# Stimulation_Testbed_Expansion_V2.net
KiCad netlist of a schematic drawn in EAGLE
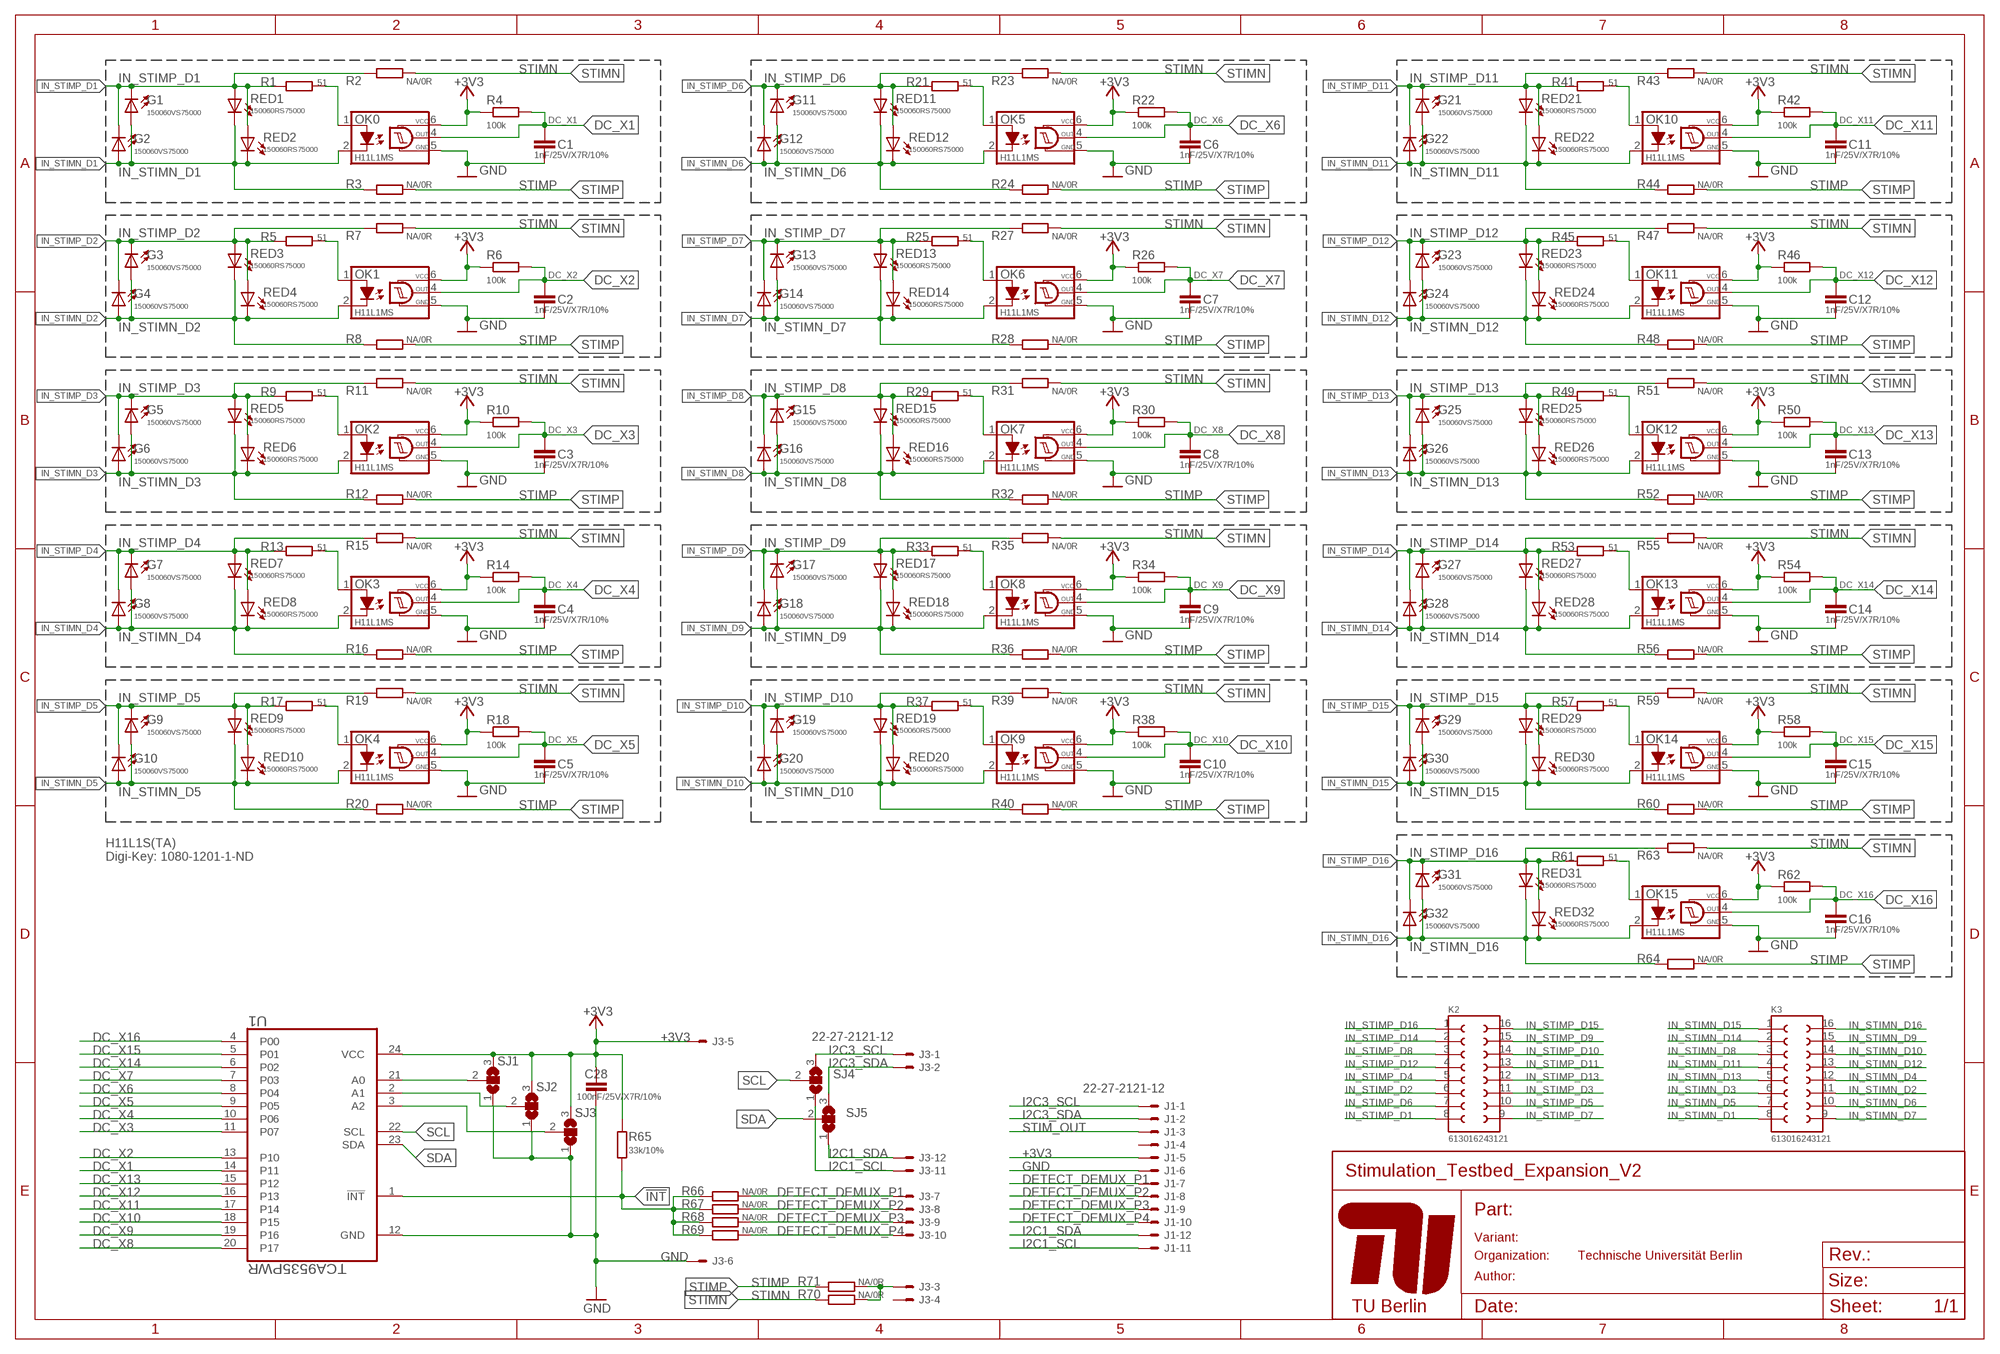
[diagram p0: schematic, sheet 1]

(export (version "E")
  (design (tool "Eeschema 10.0.6"))
  (components
    (comp (ref "C1")
      (value "1nF/25V/X7R/10%")
      (footprint "eagle-import:C0603")
      (libsource (lib "eagle-import") (part "C-EUC0603"))
    )
    (comp (ref "C2")
      (value "1nF/25V/X7R/10%")
      (footprint "eagle-import:C0603")
      (libsource (lib "eagle-import") (part "C-EUC0603"))
    )
    (comp (ref "C3")
      (value "1nF/25V/X7R/10%")
      (footprint "eagle-import:C0603")
      (libsource (lib "eagle-import") (part "C-EUC0603"))
    )
    (comp (ref "C4")
      (value "1nF/25V/X7R/10%")
      (footprint "eagle-import:C0603")
      (libsource (lib "eagle-import") (part "C-EUC0603"))
    )
    (comp (ref "C5")
      (value "1nF/25V/X7R/10%")
      (footprint "eagle-import:C0603")
      (libsource (lib "eagle-import") (part "C-EUC0603"))
    )
    (comp (ref "C6")
      (value "1nF/25V/X7R/10%")
      (footprint "eagle-import:C0603")
      (libsource (lib "eagle-import") (part "C-EUC0603"))
    )
    (comp (ref "C7")
      (value "1nF/25V/X7R/10%")
      (footprint "eagle-import:C0603")
      (libsource (lib "eagle-import") (part "C-EUC0603"))
    )
    (comp (ref "C8")
      (value "1nF/25V/X7R/10%")
      (footprint "eagle-import:C0603")
      (libsource (lib "eagle-import") (part "C-EUC0603"))
    )
    (comp (ref "C9")
      (value "1nF/25V/X7R/10%")
      (footprint "eagle-import:C0603")
      (libsource (lib "eagle-import") (part "C-EUC0603"))
    )
    (comp (ref "C10")
      (value "1nF/25V/X7R/10%")
      (footprint "eagle-import:C0603")
      (libsource (lib "eagle-import") (part "C-EUC0603"))
    )
    (comp (ref "C11")
      (value "1nF/25V/X7R/10%")
      (footprint "eagle-import:C0603")
      (libsource (lib "eagle-import") (part "C-EUC0603"))
    )
    (comp (ref "C12")
      (value "1nF/25V/X7R/10%")
      (footprint "eagle-import:C0603")
      (libsource (lib "eagle-import") (part "C-EUC0603"))
    )
    (comp (ref "C13")
      (value "1nF/25V/X7R/10%")
      (footprint "eagle-import:C0603")
      (libsource (lib "eagle-import") (part "C-EUC0603"))
    )
    (comp (ref "C14")
      (value "1nF/25V/X7R/10%")
      (footprint "eagle-import:C0603")
      (libsource (lib "eagle-import") (part "C-EUC0603"))
    )
    (comp (ref "C15")
      (value "1nF/25V/X7R/10%")
      (footprint "eagle-import:C0603")
      (libsource (lib "eagle-import") (part "C-EUC0603"))
    )
    (comp (ref "C16")
      (value "1nF/25V/X7R/10%")
      (footprint "eagle-import:C0603")
      (libsource (lib "eagle-import") (part "C-EUC0603"))
    )
    (comp (ref "C28")
      (value "100nF/25V/X7R/10%")
      (footprint "eagle-import:C0603K")
      (libsource (lib "eagle-import") (part "C-EUC0603K"))
    )
    (comp (ref "G1")
      (value "150060VS75000")
      (footprint "eagle-import:CHIPLED_0603")
      (libsource (lib "eagle-import") (part "LEDCHIPLED_0603"))
    )
    (comp (ref "G2")
      (value "150060VS75000")
      (footprint "eagle-import:CHIPLED_0603")
      (libsource (lib "eagle-import") (part "LEDCHIPLED_0603"))
    )
    (comp (ref "G3")
      (value "150060VS75000")
      (footprint "eagle-import:CHIPLED_0603")
      (libsource (lib "eagle-import") (part "LEDCHIPLED_0603"))
    )
    (comp (ref "G4")
      (value "150060VS75000")
      (footprint "eagle-import:CHIPLED_0603")
      (libsource (lib "eagle-import") (part "LEDCHIPLED_0603"))
    )
    (comp (ref "G5")
      (value "150060VS75000")
      (footprint "eagle-import:CHIPLED_0603")
      (libsource (lib "eagle-import") (part "LEDCHIPLED_0603"))
    )
    (comp (ref "G6")
      (value "150060VS75000")
      (footprint "eagle-import:CHIPLED_0603")
      (libsource (lib "eagle-import") (part "LEDCHIPLED_0603"))
    )
    (comp (ref "G7")
      (value "150060VS75000")
      (footprint "eagle-import:CHIPLED_0603")
      (libsource (lib "eagle-import") (part "LEDCHIPLED_0603"))
    )
    (comp (ref "G8")
      (value "150060VS75000")
      (footprint "eagle-import:CHIPLED_0603")
      (libsource (lib "eagle-import") (part "LEDCHIPLED_0603"))
    )
    (comp (ref "G9")
      (value "150060VS75000")
      (footprint "eagle-import:CHIPLED_0603")
      (libsource (lib "eagle-import") (part "LEDCHIPLED_0603"))
    )
    (comp (ref "G10")
      (value "150060VS75000")
      (footprint "eagle-import:CHIPLED_0603")
      (libsource (lib "eagle-import") (part "LEDCHIPLED_0603"))
    )
    (comp (ref "G11")
      (value "150060VS75000")
      (footprint "eagle-import:CHIPLED_0603")
      (libsource (lib "eagle-import") (part "LEDCHIPLED_0603"))
    )
    (comp (ref "G12")
      (value "150060VS75000")
      (footprint "eagle-import:CHIPLED_0603")
      (libsource (lib "eagle-import") (part "LEDCHIPLED_0603"))
    )
    (comp (ref "G13")
      (value "150060VS75000")
      (footprint "eagle-import:CHIPLED_0603")
      (libsource (lib "eagle-import") (part "LEDCHIPLED_0603"))
    )
    (comp (ref "G14")
      (value "150060VS75000")
      (footprint "eagle-import:CHIPLED_0603")
      (libsource (lib "eagle-import") (part "LEDCHIPLED_0603"))
    )
    (comp (ref "G15")
      (value "150060VS75000")
      (footprint "eagle-import:CHIPLED_0603")
      (libsource (lib "eagle-import") (part "LEDCHIPLED_0603"))
    )
    (comp (ref "G16")
      (value "150060VS75000")
      (footprint "eagle-import:CHIPLED_0603")
      (libsource (lib "eagle-import") (part "LEDCHIPLED_0603"))
    )
    (comp (ref "G17")
      (value "150060VS75000")
      (footprint "eagle-import:CHIPLED_0603")
      (libsource (lib "eagle-import") (part "LEDCHIPLED_0603"))
    )
    (comp (ref "G18")
      (value "150060VS75000")
      (footprint "eagle-import:CHIPLED_0603")
      (libsource (lib "eagle-import") (part "LEDCHIPLED_0603"))
    )
    (comp (ref "G19")
      (value "150060VS75000")
      (footprint "eagle-import:CHIPLED_0603")
      (libsource (lib "eagle-import") (part "LEDCHIPLED_0603"))
    )
    (comp (ref "G20")
      (value "150060VS75000")
      (footprint "eagle-import:CHIPLED_0603")
      (libsource (lib "eagle-import") (part "LEDCHIPLED_0603"))
    )
    (comp (ref "G21")
      (value "150060VS75000")
      (footprint "eagle-import:CHIPLED_0603")
      (libsource (lib "eagle-import") (part "LEDCHIPLED_0603"))
    )
    (comp (ref "G22")
      (value "150060VS75000")
      (footprint "eagle-import:CHIPLED_0603")
      (libsource (lib "eagle-import") (part "LEDCHIPLED_0603"))
    )
    (comp (ref "G23")
      (value "150060VS75000")
      (footprint "eagle-import:CHIPLED_0603")
      (libsource (lib "eagle-import") (part "LEDCHIPLED_0603"))
    )
    (comp (ref "G24")
      (value "150060VS75000")
      (footprint "eagle-import:CHIPLED_0603")
      (libsource (lib "eagle-import") (part "LEDCHIPLED_0603"))
    )
    (comp (ref "G25")
      (value "150060VS75000")
      (footprint "eagle-import:CHIPLED_0603")
      (libsource (lib "eagle-import") (part "LEDCHIPLED_0603"))
    )
    (comp (ref "G26")
      (value "150060VS75000")
      (footprint "eagle-import:CHIPLED_0603")
      (libsource (lib "eagle-import") (part "LEDCHIPLED_0603"))
    )
    (comp (ref "G27")
      (value "150060VS75000")
      (footprint "eagle-import:CHIPLED_0603")
      (libsource (lib "eagle-import") (part "LEDCHIPLED_0603"))
    )
    (comp (ref "G28")
      (value "150060VS75000")
      (footprint "eagle-import:CHIPLED_0603")
      (libsource (lib "eagle-import") (part "LEDCHIPLED_0603"))
    )
    (comp (ref "G29")
      (value "150060VS75000")
      (footprint "eagle-import:CHIPLED_0603")
      (libsource (lib "eagle-import") (part "LEDCHIPLED_0603"))
    )
    (comp (ref "G30")
      (value "150060VS75000")
      (footprint "eagle-import:CHIPLED_0603")
      (libsource (lib "eagle-import") (part "LEDCHIPLED_0603"))
    )
    (comp (ref "G31")
      (value "150060VS75000")
      (footprint "eagle-import:CHIPLED_0603")
      (libsource (lib "eagle-import") (part "LEDCHIPLED_0603"))
    )
    (comp (ref "G32")
      (value "150060VS75000")
      (footprint "eagle-import:CHIPLED_0603")
      (libsource (lib "eagle-import") (part "LEDCHIPLED_0603"))
    )
    (comp (ref "J1")
      (value "22-27-2121-12")
      (footprint "eagle-import:6410-12")
      (libsource (lib "eagle-import") (part "22-?-1227-2121"))
    )
    (comp (ref "J3")
      (value "22-27-2121-12")
      (footprint "eagle-import:6410-12")
      (libsource (lib "eagle-import") (part "22-?-1227-2121"))
    )
    (comp (ref "K2")
      (value "613016243121")
      (footprint "eagle-import:613016243121")
      (libsource (lib "eagle-import") (part "613016243121"))
    )
    (comp (ref "K3")
      (value "613016243121")
      (footprint "eagle-import:613016243121")
      (libsource (lib "eagle-import") (part "613016243121"))
    )
    (comp (ref "OK0")
      (value "H11L1MS")
      (footprint "eagle-import:DIL6-SMD")
      (libsource (lib "eagle-import") (part "H11LMS1"))
    )
    (comp (ref "OK1")
      (value "H11L1MS")
      (footprint "eagle-import:DIL6-SMD")
      (libsource (lib "eagle-import") (part "H11LMS1"))
    )
    (comp (ref "OK2")
      (value "H11L1MS")
      (footprint "eagle-import:DIL6-SMD")
      (libsource (lib "eagle-import") (part "H11LMS1"))
    )
    (comp (ref "OK3")
      (value "H11L1MS")
      (footprint "eagle-import:DIL6-SMD")
      (libsource (lib "eagle-import") (part "H11LMS1"))
    )
    (comp (ref "OK4")
      (value "H11L1MS")
      (footprint "eagle-import:DIL6-SMD")
      (libsource (lib "eagle-import") (part "H11LMS1"))
    )
    (comp (ref "OK5")
      (value "H11L1MS")
      (footprint "eagle-import:DIL6-SMD")
      (libsource (lib "eagle-import") (part "H11LMS1"))
    )
    (comp (ref "OK6")
      (value "H11L1MS")
      (footprint "eagle-import:DIL6-SMD")
      (libsource (lib "eagle-import") (part "H11LMS1"))
    )
    (comp (ref "OK7")
      (value "H11L1MS")
      (footprint "eagle-import:DIL6-SMD")
      (libsource (lib "eagle-import") (part "H11LMS1"))
    )
    (comp (ref "OK8")
      (value "H11L1MS")
      (footprint "eagle-import:DIL6-SMD")
      (libsource (lib "eagle-import") (part "H11LMS1"))
    )
    (comp (ref "OK9")
      (value "H11L1MS")
      (footprint "eagle-import:DIL6-SMD")
      (libsource (lib "eagle-import") (part "H11LMS1"))
    )
    (comp (ref "OK10")
      (value "H11L1MS")
      (footprint "eagle-import:DIL6-SMD")
      (libsource (lib "eagle-import") (part "H11LMS1"))
    )
    (comp (ref "OK11")
      (value "H11L1MS")
      (footprint "eagle-import:DIL6-SMD")
      (libsource (lib "eagle-import") (part "H11LMS1"))
    )
    (comp (ref "OK12")
      (value "H11L1MS")
      (footprint "eagle-import:DIL6-SMD")
      (libsource (lib "eagle-import") (part "H11LMS1"))
    )
    (comp (ref "OK13")
      (value "H11L1MS")
      (footprint "eagle-import:DIL6-SMD")
      (libsource (lib "eagle-import") (part "H11LMS1"))
    )
    (comp (ref "OK14")
      (value "H11L1MS")
      (footprint "eagle-import:DIL6-SMD")
      (libsource (lib "eagle-import") (part "H11LMS1"))
    )
    (comp (ref "OK15")
      (value "H11L1MS")
      (footprint "eagle-import:DIL6-SMD")
      (libsource (lib "eagle-import") (part "H11LMS1"))
    )
    (comp (ref "R1")
      (value "51")
      (footprint "eagle-import:R0603")
      (libsource (lib "eagle-import") (part "R-EU_R0603"))
    )
    (comp (ref "R2")
      (value "NA/0R")
      (footprint "eagle-import:R0603")
      (libsource (lib "eagle-import") (part "R-EU_R0603"))
    )
    (comp (ref "R3")
      (value "NA/0R")
      (footprint "eagle-import:R0603")
      (libsource (lib "eagle-import") (part "R-EU_R0603"))
    )
    (comp (ref "R4")
      (value "100k")
      (footprint "eagle-import:R0603")
      (libsource (lib "eagle-import") (part "R-EU_R0603"))
    )
    (comp (ref "R5")
      (value "51")
      (footprint "eagle-import:R0603")
      (libsource (lib "eagle-import") (part "R-EU_R0603"))
    )
    (comp (ref "R6")
      (value "100k")
      (footprint "eagle-import:R0603")
      (libsource (lib "eagle-import") (part "R-EU_R0603"))
    )
    (comp (ref "R7")
      (value "NA/0R")
      (footprint "eagle-import:R0603")
      (libsource (lib "eagle-import") (part "R-EU_R0603"))
    )
    (comp (ref "R8")
      (value "NA/0R")
      (footprint "eagle-import:R0603")
      (libsource (lib "eagle-import") (part "R-EU_R0603"))
    )
    (comp (ref "R9")
      (value "51")
      (footprint "eagle-import:R0603")
      (libsource (lib "eagle-import") (part "R-EU_R0603"))
    )
    (comp (ref "R10")
      (value "100k")
      (footprint "eagle-import:R0603")
      (libsource (lib "eagle-import") (part "R-EU_R0603"))
    )
    (comp (ref "R11")
      (value "NA/0R")
      (footprint "eagle-import:R0603")
      (libsource (lib "eagle-import") (part "R-EU_R0603"))
    )
    (comp (ref "R12")
      (value "NA/0R")
      (footprint "eagle-import:R0603")
      (libsource (lib "eagle-import") (part "R-EU_R0603"))
    )
    (comp (ref "R13")
      (value "51")
      (footprint "eagle-import:R0603")
      (libsource (lib "eagle-import") (part "R-EU_R0603"))
    )
    (comp (ref "R14")
      (value "100k")
      (footprint "eagle-import:R0603")
      (libsource (lib "eagle-import") (part "R-EU_R0603"))
    )
    (comp (ref "R15")
      (value "NA/0R")
      (footprint "eagle-import:R0603")
      (libsource (lib "eagle-import") (part "R-EU_R0603"))
    )
    (comp (ref "R16")
      (value "NA/0R")
      (footprint "eagle-import:R0603")
      (libsource (lib "eagle-import") (part "R-EU_R0603"))
    )
    (comp (ref "R17")
      (value "51")
      (footprint "eagle-import:R0603")
      (libsource (lib "eagle-import") (part "R-EU_R0603"))
    )
    (comp (ref "R18")
      (value "100k")
      (footprint "eagle-import:R0603")
      (libsource (lib "eagle-import") (part "R-EU_R0603"))
    )
    (comp (ref "R19")
      (value "NA/0R")
      (footprint "eagle-import:R0603")
      (libsource (lib "eagle-import") (part "R-EU_R0603"))
    )
    (comp (ref "R20")
      (value "NA/0R")
      (footprint "eagle-import:R0603")
      (libsource (lib "eagle-import") (part "R-EU_R0603"))
    )
    (comp (ref "R21")
      (value "51")
      (footprint "eagle-import:R0603")
      (libsource (lib "eagle-import") (part "R-EU_R0603"))
    )
    (comp (ref "R22")
      (value "100k")
      (footprint "eagle-import:R0603")
      (libsource (lib "eagle-import") (part "R-EU_R0603"))
    )
    (comp (ref "R23")
      (value "NA/0R")
      (footprint "eagle-import:R0603")
      (libsource (lib "eagle-import") (part "R-EU_R0603"))
    )
    (comp (ref "R24")
      (value "NA/0R")
      (footprint "eagle-import:R0603")
      (libsource (lib "eagle-import") (part "R-EU_R0603"))
    )
    (comp (ref "R25")
      (value "51")
      (footprint "eagle-import:R0603")
      (libsource (lib "eagle-import") (part "R-EU_R0603"))
    )
    (comp (ref "R26")
      (value "100k")
      (footprint "eagle-import:R0603")
      (libsource (lib "eagle-import") (part "R-EU_R0603"))
    )
    (comp (ref "R27")
      (value "NA/0R")
      (footprint "eagle-import:R0603")
      (libsource (lib "eagle-import") (part "R-EU_R0603"))
    )
    (comp (ref "R28")
      (value "NA/0R")
      (footprint "eagle-import:R0603")
      (libsource (lib "eagle-import") (part "R-EU_R0603"))
    )
    (comp (ref "R29")
      (value "51")
      (footprint "eagle-import:R0603")
      (libsource (lib "eagle-import") (part "R-EU_R0603"))
    )
    (comp (ref "R30")
      (value "100k")
      (footprint "eagle-import:R0603")
      (libsource (lib "eagle-import") (part "R-EU_R0603"))
    )
    (comp (ref "R31")
      (value "NA/0R")
      (footprint "eagle-import:R0603")
      (libsource (lib "eagle-import") (part "R-EU_R0603"))
    )
    (comp (ref "R32")
      (value "NA/0R")
      (footprint "eagle-import:R0603")
      (libsource (lib "eagle-import") (part "R-EU_R0603"))
    )
    (comp (ref "R33")
      (value "51")
      (footprint "eagle-import:R0603")
      (libsource (lib "eagle-import") (part "R-EU_R0603"))
    )
    (comp (ref "R34")
      (value "100k")
      (footprint "eagle-import:R0603")
      (libsource (lib "eagle-import") (part "R-EU_R0603"))
    )
    (comp (ref "R35")
      (value "NA/0R")
      (footprint "eagle-import:R0603")
      (libsource (lib "eagle-import") (part "R-EU_R0603"))
    )
    (comp (ref "R36")
      (value "NA/0R")
      (footprint "eagle-import:R0603")
      (libsource (lib "eagle-import") (part "R-EU_R0603"))
    )
    (comp (ref "R37")
      (value "51")
      (footprint "eagle-import:R0603")
      (libsource (lib "eagle-import") (part "R-EU_R0603"))
    )
    (comp (ref "R38")
      (value "100k")
      (footprint "eagle-import:R0603")
      (libsource (lib "eagle-import") (part "R-EU_R0603"))
    )
    (comp (ref "R39")
      (value "NA/0R")
      (footprint "eagle-import:R0603")
      (libsource (lib "eagle-import") (part "R-EU_R0603"))
    )
    (comp (ref "R40")
      (value "NA/0R")
      (footprint "eagle-import:R0603")
      (libsource (lib "eagle-import") (part "R-EU_R0603"))
    )
    (comp (ref "R41")
      (value "51")
      (footprint "eagle-import:R0603")
      (libsource (lib "eagle-import") (part "R-EU_R0603"))
    )
    (comp (ref "R42")
      (value "100k")
      (footprint "eagle-import:R0603")
      (libsource (lib "eagle-import") (part "R-EU_R0603"))
    )
    (comp (ref "R43")
      (value "NA/0R")
      (footprint "eagle-import:R0603")
      (libsource (lib "eagle-import") (part "R-EU_R0603"))
    )
    (comp (ref "R44")
      (value "NA/0R")
      (footprint "eagle-import:R0603")
      (libsource (lib "eagle-import") (part "R-EU_R0603"))
    )
    (comp (ref "R45")
      (value "51")
      (footprint "eagle-import:R0603")
      (libsource (lib "eagle-import") (part "R-EU_R0603"))
    )
    (comp (ref "R46")
      (value "100k")
      (footprint "eagle-import:R0603")
      (libsource (lib "eagle-import") (part "R-EU_R0603"))
    )
    (comp (ref "R47")
      (value "NA/0R")
      (footprint "eagle-import:R0603")
      (libsource (lib "eagle-import") (part "R-EU_R0603"))
    )
    (comp (ref "R48")
      (value "NA/0R")
      (footprint "eagle-import:R0603")
      (libsource (lib "eagle-import") (part "R-EU_R0603"))
    )
    (comp (ref "R49")
      (value "51")
      (footprint "eagle-import:R0603")
      (libsource (lib "eagle-import") (part "R-EU_R0603"))
    )
    (comp (ref "R50")
      (value "100k")
      (footprint "eagle-import:R0603")
      (libsource (lib "eagle-import") (part "R-EU_R0603"))
    )
    (comp (ref "R51")
      (value "NA/0R")
      (footprint "eagle-import:R0603")
      (libsource (lib "eagle-import") (part "R-EU_R0603"))
    )
    (comp (ref "R52")
      (value "NA/0R")
      (footprint "eagle-import:R0603")
      (libsource (lib "eagle-import") (part "R-EU_R0603"))
    )
    (comp (ref "R53")
      (value "51")
      (footprint "eagle-import:R0603")
      (libsource (lib "eagle-import") (part "R-EU_R0603"))
    )
    (comp (ref "R54")
      (value "100k")
      (footprint "eagle-import:R0603")
      (libsource (lib "eagle-import") (part "R-EU_R0603"))
    )
    (comp (ref "R55")
      (value "NA/0R")
      (footprint "eagle-import:R0603")
      (libsource (lib "eagle-import") (part "R-EU_R0603"))
    )
    (comp (ref "R56")
      (value "NA/0R")
      (footprint "eagle-import:R0603")
      (libsource (lib "eagle-import") (part "R-EU_R0603"))
    )
    (comp (ref "R57")
      (value "51")
      (footprint "eagle-import:R0603")
      (libsource (lib "eagle-import") (part "R-EU_R0603"))
    )
    (comp (ref "R58")
      (value "100k")
      (footprint "eagle-import:R0603")
      (libsource (lib "eagle-import") (part "R-EU_R0603"))
    )
    (comp (ref "R59")
      (value "NA/0R")
      (footprint "eagle-import:R0603")
      (libsource (lib "eagle-import") (part "R-EU_R0603"))
    )
    (comp (ref "R60")
      (value "NA/0R")
      (footprint "eagle-import:R0603")
      (libsource (lib "eagle-import") (part "R-EU_R0603"))
    )
    (comp (ref "R61")
      (value "51")
      (footprint "eagle-import:R0603")
      (libsource (lib "eagle-import") (part "R-EU_R0603"))
    )
    (comp (ref "R62")
      (value "100k")
      (footprint "eagle-import:R0603")
      (libsource (lib "eagle-import") (part "R-EU_R0603"))
    )
    (comp (ref "R63")
      (value "NA/0R")
      (footprint "eagle-import:R0603")
      (libsource (lib "eagle-import") (part "R-EU_R0603"))
    )
    (comp (ref "R64")
      (value "NA/0R")
      (footprint "eagle-import:R0603")
      (libsource (lib "eagle-import") (part "R-EU_R0603"))
    )
    (comp (ref "R65")
      (value "33k/10%")
      (footprint "eagle-import:R0603")
      (libsource (lib "eagle-import") (part "R-EU_R0603"))
    )
    (comp (ref "R66")
      (value "NA/0R")
      (footprint "eagle-import:R0603")
      (libsource (lib "eagle-import") (part "R-EU_R0603"))
    )
    (comp (ref "R67")
      (value "NA/0R")
      (footprint "eagle-import:R0603")
      (libsource (lib "eagle-import") (part "R-EU_R0603"))
    )
    (comp (ref "R68")
      (value "NA/0R")
      (footprint "eagle-import:R0603")
      (libsource (lib "eagle-import") (part "R-EU_R0603"))
    )
    (comp (ref "R69")
      (value "NA/0R")
      (footprint "eagle-import:R0603")
      (libsource (lib "eagle-import") (part "R-EU_R0603"))
    )
    (comp (ref "R70")
      (value "NA/0R")
      (footprint "eagle-import:R0603")
      (libsource (lib "eagle-import") (part "R-EU_R0603"))
    )
    (comp (ref "R71")
      (value "NA/0R")
      (footprint "eagle-import:R0603")
      (libsource (lib "eagle-import") (part "R-EU_R0603"))
    )
    (comp (ref "RED1")
      (value "150060RS75000")
      (footprint "eagle-import:CHIP-LED0603")
      (libsource (lib "eagle-import") (part "LEDCHIP-LED0603"))
    )
    (comp (ref "RED2")
      (value "150060RS75000")
      (footprint "eagle-import:CHIP-LED0603")
      (libsource (lib "eagle-import") (part "LEDCHIP-LED0603"))
    )
    (comp (ref "RED3")
      (value "150060RS75000")
      (footprint "eagle-import:CHIP-LED0603")
      (libsource (lib "eagle-import") (part "LEDCHIP-LED0603"))
    )
    (comp (ref "RED4")
      (value "150060RS75000")
      (footprint "eagle-import:CHIP-LED0603")
      (libsource (lib "eagle-import") (part "LEDCHIP-LED0603"))
    )
    (comp (ref "RED5")
      (value "150060RS75000")
      (footprint "eagle-import:CHIP-LED0603")
      (libsource (lib "eagle-import") (part "LEDCHIP-LED0603"))
    )
    (comp (ref "RED6")
      (value "150060RS75000")
      (footprint "eagle-import:CHIP-LED0603")
      (libsource (lib "eagle-import") (part "LEDCHIP-LED0603"))
    )
    (comp (ref "RED7")
      (value "150060RS75000")
      (footprint "eagle-import:CHIP-LED0603")
      (libsource (lib "eagle-import") (part "LEDCHIP-LED0603"))
    )
    (comp (ref "RED8")
      (value "150060RS75000")
      (footprint "eagle-import:CHIP-LED0603")
      (libsource (lib "eagle-import") (part "LEDCHIP-LED0603"))
    )
    (comp (ref "RED9")
      (value "150060RS75000")
      (footprint "eagle-import:CHIP-LED0603")
      (libsource (lib "eagle-import") (part "LEDCHIP-LED0603"))
    )
    (comp (ref "RED10")
      (value "150060RS75000")
      (footprint "eagle-import:CHIP-LED0603")
      (libsource (lib "eagle-import") (part "LEDCHIP-LED0603"))
    )
    (comp (ref "RED11")
      (value "150060RS75000")
      (footprint "eagle-import:CHIP-LED0603")
      (libsource (lib "eagle-import") (part "LEDCHIP-LED0603"))
    )
    (comp (ref "RED12")
      (value "150060RS75000")
      (footprint "eagle-import:CHIP-LED0603")
      (libsource (lib "eagle-import") (part "LEDCHIP-LED0603"))
    )
    (comp (ref "RED13")
      (value "150060RS75000")
      (footprint "eagle-import:CHIP-LED0603")
      (libsource (lib "eagle-import") (part "LEDCHIP-LED0603"))
    )
    (comp (ref "RED14")
      (value "150060RS75000")
      (footprint "eagle-import:CHIP-LED0603")
      (libsource (lib "eagle-import") (part "LEDCHIP-LED0603"))
    )
    (comp (ref "RED15")
      (value "150060RS75000")
      (footprint "eagle-import:CHIP-LED0603")
      (libsource (lib "eagle-import") (part "LEDCHIP-LED0603"))
    )
    (comp (ref "RED16")
      (value "150060RS75000")
      (footprint "eagle-import:CHIP-LED0603")
      (libsource (lib "eagle-import") (part "LEDCHIP-LED0603"))
    )
    (comp (ref "RED17")
      (value "150060RS75000")
      (footprint "eagle-import:CHIP-LED0603")
      (libsource (lib "eagle-import") (part "LEDCHIP-LED0603"))
    )
    (comp (ref "RED18")
      (value "150060RS75000")
      (footprint "eagle-import:CHIP-LED0603")
      (libsource (lib "eagle-import") (part "LEDCHIP-LED0603"))
    )
    (comp (ref "RED19")
      (value "150060RS75000")
      (footprint "eagle-import:CHIP-LED0603")
      (libsource (lib "eagle-import") (part "LEDCHIP-LED0603"))
    )
    (comp (ref "RED20")
      (value "150060RS75000")
      (footprint "eagle-import:CHIP-LED0603")
      (libsource (lib "eagle-import") (part "LEDCHIP-LED0603"))
    )
    (comp (ref "RED21")
      (value "150060RS75000")
      (footprint "eagle-import:CHIP-LED0603")
      (libsource (lib "eagle-import") (part "LEDCHIP-LED0603"))
    )
    (comp (ref "RED22")
      (value "150060RS75000")
      (footprint "eagle-import:CHIP-LED0603")
      (libsource (lib "eagle-import") (part "LEDCHIP-LED0603"))
    )
    (comp (ref "RED23")
      (value "150060RS75000")
      (footprint "eagle-import:CHIP-LED0603")
      (libsource (lib "eagle-import") (part "LEDCHIP-LED0603"))
    )
    (comp (ref "RED24")
      (value "150060RS75000")
      (footprint "eagle-import:CHIP-LED0603")
      (libsource (lib "eagle-import") (part "LEDCHIP-LED0603"))
    )
    (comp (ref "RED25")
      (value "150060RS75000")
      (footprint "eagle-import:CHIP-LED0603")
      (libsource (lib "eagle-import") (part "LEDCHIP-LED0603"))
    )
    (comp (ref "RED26")
      (value "150060RS75000")
      (footprint "eagle-import:CHIP-LED0603")
      (libsource (lib "eagle-import") (part "LEDCHIP-LED0603"))
    )
    (comp (ref "RED27")
      (value "150060RS75000")
      (footprint "eagle-import:CHIP-LED0603")
      (libsource (lib "eagle-import") (part "LEDCHIP-LED0603"))
    )
    (comp (ref "RED28")
      (value "150060RS75000")
      (footprint "eagle-import:CHIP-LED0603")
      (libsource (lib "eagle-import") (part "LEDCHIP-LED0603"))
    )
    (comp (ref "RED29")
      (value "150060RS75000")
      (footprint "eagle-import:CHIP-LED0603")
      (libsource (lib "eagle-import") (part "LEDCHIP-LED0603"))
    )
    (comp (ref "RED30")
      (value "150060RS75000")
      (footprint "eagle-import:CHIP-LED0603")
      (libsource (lib "eagle-import") (part "LEDCHIP-LED0603"))
    )
    (comp (ref "RED31")
      (value "150060RS75000")
      (footprint "eagle-import:CHIP-LED0603")
      (libsource (lib "eagle-import") (part "LEDCHIP-LED0603"))
    )
    (comp (ref "RED32")
      (value "150060RS75000")
      (footprint "eagle-import:CHIP-LED0603")
      (libsource (lib "eagle-import") (part "LEDCHIP-LED0603"))
    )
    (comp (ref "SJ1")
      (value "SJ2W")
      (footprint "eagle-import:SJ_2")
      (libsource (lib "eagle-import") (part "SJ2W"))
    )
    (comp (ref "SJ2")
      (value "SJ2W")
      (footprint "eagle-import:SJ_2")
      (libsource (lib "eagle-import") (part "SJ2W"))
    )
    (comp (ref "SJ3")
      (value "SJ2W")
      (footprint "eagle-import:SJ_2")
      (libsource (lib "eagle-import") (part "SJ2W"))
    )
    (comp (ref "SJ4")
      (value "SJ2W")
      (footprint "eagle-import:SJ_2")
      (libsource (lib "eagle-import") (part "SJ2W"))
    )
    (comp (ref "SJ5")
      (value "SJ2W")
      (footprint "eagle-import:SJ_2")
      (libsource (lib "eagle-import") (part "SJ2W"))
    )
    (comp (ref "U1")
      (value "TCA9535PWR")
      (footprint "eagle-import:SOP65P640X120-24N")
      (fields (field (name "MF") "Texas Instruments"))
      (libsource (lib "eagle-import") (part "TCA9535PWR"))
    )
  )
  (nets
    (net (code "1") (name "+3V3") (class "Default")
      (node (ref "C28") (pin "1") (pinfunction "1_1") (pintype "passive"))
      (node (ref "J1") (pin "5") (pinfunction "S_5") (pintype "passive"))
      (node (ref "J3") (pin "5") (pinfunction "S_5") (pintype "passive"))
      (node (ref "OK0") (pin "6") (pinfunction "VCC_6") (pintype "power_in"))
      (node (ref "OK1") (pin "6") (pinfunction "VCC_6") (pintype "power_in"))
      (node (ref "OK10") (pin "6") (pinfunction "VCC_6") (pintype "power_in"))
      (node (ref "OK11") (pin "6") (pinfunction "VCC_6") (pintype "power_in"))
      (node (ref "OK12") (pin "6") (pinfunction "VCC_6") (pintype "power_in"))
      (node (ref "OK13") (pin "6") (pinfunction "VCC_6") (pintype "power_in"))
      (node (ref "OK14") (pin "6") (pinfunction "VCC_6") (pintype "power_in"))
      (node (ref "OK15") (pin "6") (pinfunction "VCC_6") (pintype "power_in"))
      (node (ref "OK2") (pin "6") (pinfunction "VCC_6") (pintype "power_in"))
      (node (ref "OK3") (pin "6") (pinfunction "VCC_6") (pintype "power_in"))
      (node (ref "OK4") (pin "6") (pinfunction "VCC_6") (pintype "power_in"))
      (node (ref "OK5") (pin "6") (pinfunction "VCC_6") (pintype "power_in"))
      (node (ref "OK6") (pin "6") (pinfunction "VCC_6") (pintype "power_in"))
      (node (ref "OK7") (pin "6") (pinfunction "VCC_6") (pintype "power_in"))
      (node (ref "OK8") (pin "6") (pinfunction "VCC_6") (pintype "power_in"))
      (node (ref "OK9") (pin "6") (pinfunction "VCC_6") (pintype "power_in"))
      (node (ref "R10") (pin "1") (pinfunction "1_1") (pintype "passive"))
      (node (ref "R14") (pin "1") (pinfunction "1_1") (pintype "passive"))
      (node (ref "R18") (pin "1") (pinfunction "1_1") (pintype "passive"))
      (node (ref "R22") (pin "1") (pinfunction "1_1") (pintype "passive"))
      (node (ref "R26") (pin "1") (pinfunction "1_1") (pintype "passive"))
      (node (ref "R30") (pin "1") (pinfunction "1_1") (pintype "passive"))
      (node (ref "R34") (pin "1") (pinfunction "1_1") (pintype "passive"))
      (node (ref "R38") (pin "1") (pinfunction "1_1") (pintype "passive"))
      (node (ref "R4") (pin "1") (pinfunction "1_1") (pintype "passive"))
      (node (ref "R42") (pin "1") (pinfunction "1_1") (pintype "passive"))
      (node (ref "R46") (pin "1") (pinfunction "1_1") (pintype "passive"))
      (node (ref "R50") (pin "1") (pinfunction "1_1") (pintype "passive"))
      (node (ref "R54") (pin "1") (pinfunction "1_1") (pintype "passive"))
      (node (ref "R58") (pin "1") (pinfunction "1_1") (pintype "passive"))
      (node (ref "R6") (pin "1") (pinfunction "1_1") (pintype "passive"))
      (node (ref "R62") (pin "1") (pinfunction "1_1") (pintype "passive"))
      (node (ref "R65") (pin "2") (pinfunction "2_2") (pintype "passive"))
      (node (ref "SJ1") (pin "3") (pinfunction "3_3") (pintype "passive"))
      (node (ref "SJ2") (pin "3") (pinfunction "3_3") (pintype "passive"))
      (node (ref "SJ3") (pin "3") (pinfunction "3_3") (pintype "passive"))
      (node (ref "U1") (pin "24") (pinfunction "VCC_24") (pintype "power_in"))
    )
    (net (code "2") (name "/DETECT_DEMUX_P1") (class "Default")
      (node (ref "J1") (pin "7") (pinfunction "S_7") (pintype "passive"))
      (node (ref "J3") (pin "7") (pinfunction "S_7") (pintype "passive"))
      (node (ref "R66") (pin "1") (pinfunction "1_1") (pintype "passive"))
    )
    (net (code "3") (name "/DETECT_DEMUX_P2") (class "Default")
      (node (ref "J1") (pin "8") (pinfunction "S_8") (pintype "passive"))
      (node (ref "J3") (pin "8") (pinfunction "S_8") (pintype "passive"))
      (node (ref "R67") (pin "1") (pinfunction "1_1") (pintype "passive"))
    )
    (net (code "4") (name "/DETECT_DEMUX_P3") (class "Default")
      (node (ref "J1") (pin "9") (pinfunction "S_9") (pintype "passive"))
      (node (ref "J3") (pin "9") (pinfunction "S_9") (pintype "passive"))
      (node (ref "R68") (pin "1") (pinfunction "1_1") (pintype "passive"))
    )
    (net (code "5") (name "/DETECT_DEMUX_P4") (class "Default")
      (node (ref "J1") (pin "10") (pinfunction "S_10") (pintype "passive"))
      (node (ref "J3") (pin "10") (pinfunction "S_10") (pintype "passive"))
      (node (ref "R69") (pin "1") (pinfunction "1_1") (pintype "passive"))
    )
    (net (code "6") (name "/I2C1_SCL") (class "Default")
      (node (ref "J1") (pin "11") (pinfunction "S_11") (pintype "passive"))
      (node (ref "J3") (pin "11") (pinfunction "S_11") (pintype "passive"))
      (node (ref "SJ4") (pin "1") (pinfunction "1_1") (pintype "passive"))
    )
    (net (code "7") (name "/I2C1_SDA") (class "Default")
      (node (ref "J1") (pin "12") (pinfunction "S_12") (pintype "passive"))
      (node (ref "J3") (pin "12") (pinfunction "S_12") (pintype "passive"))
      (node (ref "SJ5") (pin "1") (pinfunction "1_1") (pintype "passive"))
    )
    (net (code "8") (name "/I2C3_SCL") (class "Default")
      (node (ref "J1") (pin "1") (pinfunction "S_1") (pintype "passive"))
      (node (ref "J3") (pin "1") (pinfunction "S_1") (pintype "passive"))
      (node (ref "SJ4") (pin "3") (pinfunction "3_3") (pintype "passive"))
    )
    (net (code "9") (name "/I2C3_SDA") (class "Default")
      (node (ref "J1") (pin "2") (pinfunction "S_2") (pintype "passive"))
      (node (ref "J3") (pin "2") (pinfunction "S_2") (pintype "passive"))
      (node (ref "SJ5") (pin "3") (pinfunction "3_3") (pintype "passive"))
    )
    (net (code "10") (name "/STIM_OUT") (class "Default")
      (node (ref "J1") (pin "3") (pinfunction "S_3") (pintype "passive"))
      (node (ref "J3") (pin "3") (pinfunction "S_3") (pintype "passive"))
      (node (ref "R70") (pin "1") (pinfunction "1_1") (pintype "passive"))
      (node (ref "R71") (pin "1") (pinfunction "1_1") (pintype "passive"))
    )
    (net (code "11") (name "/~{INT}") (class "Default")
      (node (ref "R65") (pin "1") (pinfunction "1_1") (pintype "passive"))
      (node (ref "R66") (pin "2") (pinfunction "2_2") (pintype "passive"))
      (node (ref "R67") (pin "2") (pinfunction "2_2") (pintype "passive"))
      (node (ref "R68") (pin "2") (pinfunction "2_2") (pintype "passive"))
      (node (ref "R69") (pin "2") (pinfunction "2_2") (pintype "passive"))
      (node (ref "U1") (pin "1") (pinfunction "~{INT}_1") (pintype "output"))
    )
    (net (code "12") (name "DC_X1") (class "Default")
      (node (ref "C1") (pin "1") (pinfunction "1_1") (pintype "passive"))
      (node (ref "OK0") (pin "4") (pinfunction "OUT_4") (pintype "output"))
      (node (ref "R4") (pin "2") (pinfunction "2_2") (pintype "passive"))
      (node (ref "U1") (pin "14") (pinfunction "P11_14") (pintype "bidirectional"))
    )
    (net (code "13") (name "DC_X2") (class "Default")
      (node (ref "C2") (pin "1") (pinfunction "1_1") (pintype "passive"))
      (node (ref "OK1") (pin "4") (pinfunction "OUT_4") (pintype "output"))
      (node (ref "R6") (pin "2") (pinfunction "2_2") (pintype "passive"))
      (node (ref "U1") (pin "13") (pinfunction "P10_13") (pintype "bidirectional"))
    )
    (net (code "14") (name "DC_X3") (class "Default")
      (node (ref "C3") (pin "1") (pinfunction "1_1") (pintype "passive"))
      (node (ref "OK2") (pin "4") (pinfunction "OUT_4") (pintype "output"))
      (node (ref "R10") (pin "2") (pinfunction "2_2") (pintype "passive"))
      (node (ref "U1") (pin "11") (pinfunction "P07_11") (pintype "bidirectional"))
    )
    (net (code "15") (name "DC_X4") (class "Default")
      (node (ref "C4") (pin "1") (pinfunction "1_1") (pintype "passive"))
      (node (ref "OK3") (pin "4") (pinfunction "OUT_4") (pintype "output"))
      (node (ref "R14") (pin "2") (pinfunction "2_2") (pintype "passive"))
      (node (ref "U1") (pin "10") (pinfunction "P06_10") (pintype "bidirectional"))
    )
    (net (code "16") (name "DC_X5") (class "Default")
      (node (ref "C5") (pin "1") (pinfunction "1_1") (pintype "passive"))
      (node (ref "OK4") (pin "4") (pinfunction "OUT_4") (pintype "output"))
      (node (ref "R18") (pin "2") (pinfunction "2_2") (pintype "passive"))
      (node (ref "U1") (pin "9") (pinfunction "P05_9") (pintype "bidirectional"))
    )
    (net (code "17") (name "DC_X6") (class "Default")
      (node (ref "C6") (pin "1") (pinfunction "1_1") (pintype "passive"))
      (node (ref "OK5") (pin "4") (pinfunction "OUT_4") (pintype "output"))
      (node (ref "R22") (pin "2") (pinfunction "2_2") (pintype "passive"))
      (node (ref "U1") (pin "8") (pinfunction "P04_8") (pintype "bidirectional"))
    )
    (net (code "18") (name "DC_X7") (class "Default")
      (node (ref "C7") (pin "1") (pinfunction "1_1") (pintype "passive"))
      (node (ref "OK6") (pin "4") (pinfunction "OUT_4") (pintype "output"))
      (node (ref "R26") (pin "2") (pinfunction "2_2") (pintype "passive"))
      (node (ref "U1") (pin "7") (pinfunction "P03_7") (pintype "bidirectional"))
    )
    (net (code "19") (name "DC_X8") (class "Default")
      (node (ref "C8") (pin "1") (pinfunction "1_1") (pintype "passive"))
      (node (ref "OK7") (pin "4") (pinfunction "OUT_4") (pintype "output"))
      (node (ref "R30") (pin "2") (pinfunction "2_2") (pintype "passive"))
      (node (ref "U1") (pin "20") (pinfunction "P17_20") (pintype "bidirectional"))
    )
    (net (code "20") (name "DC_X9") (class "Default")
      (node (ref "C9") (pin "1") (pinfunction "1_1") (pintype "passive"))
      (node (ref "OK8") (pin "4") (pinfunction "OUT_4") (pintype "output"))
      (node (ref "R34") (pin "2") (pinfunction "2_2") (pintype "passive"))
      (node (ref "U1") (pin "19") (pinfunction "P16_19") (pintype "bidirectional"))
    )
    (net (code "21") (name "DC_X10") (class "Default")
      (node (ref "C10") (pin "1") (pinfunction "1_1") (pintype "passive"))
      (node (ref "OK9") (pin "4") (pinfunction "OUT_4") (pintype "output"))
      (node (ref "R38") (pin "2") (pinfunction "2_2") (pintype "passive"))
      (node (ref "U1") (pin "18") (pinfunction "P15_18") (pintype "bidirectional"))
    )
    (net (code "22") (name "DC_X11") (class "Default")
      (node (ref "C11") (pin "1") (pinfunction "1_1") (pintype "passive"))
      (node (ref "OK10") (pin "4") (pinfunction "OUT_4") (pintype "output"))
      (node (ref "R42") (pin "2") (pinfunction "2_2") (pintype "passive"))
      (node (ref "U1") (pin "17") (pinfunction "P14_17") (pintype "bidirectional"))
    )
    (net (code "23") (name "DC_X12") (class "Default")
      (node (ref "C12") (pin "1") (pinfunction "1_1") (pintype "passive"))
      (node (ref "OK11") (pin "4") (pinfunction "OUT_4") (pintype "output"))
      (node (ref "R46") (pin "2") (pinfunction "2_2") (pintype "passive"))
      (node (ref "U1") (pin "16") (pinfunction "P13_16") (pintype "bidirectional"))
    )
    (net (code "24") (name "DC_X13") (class "Default")
      (node (ref "C13") (pin "1") (pinfunction "1_1") (pintype "passive"))
      (node (ref "OK12") (pin "4") (pinfunction "OUT_4") (pintype "output"))
      (node (ref "R50") (pin "2") (pinfunction "2_2") (pintype "passive"))
      (node (ref "U1") (pin "15") (pinfunction "P12_15") (pintype "bidirectional"))
    )
    (net (code "25") (name "DC_X14") (class "Default")
      (node (ref "C14") (pin "1") (pinfunction "1_1") (pintype "passive"))
      (node (ref "OK13") (pin "4") (pinfunction "OUT_4") (pintype "output"))
      (node (ref "R54") (pin "2") (pinfunction "2_2") (pintype "passive"))
      (node (ref "U1") (pin "6") (pinfunction "P02_6") (pintype "bidirectional"))
    )
    (net (code "26") (name "DC_X15") (class "Default")
      (node (ref "C15") (pin "1") (pinfunction "1_1") (pintype "passive"))
      (node (ref "OK14") (pin "4") (pinfunction "OUT_4") (pintype "output"))
      (node (ref "R58") (pin "2") (pinfunction "2_2") (pintype "passive"))
      (node (ref "U1") (pin "5") (pinfunction "P01_5") (pintype "bidirectional"))
    )
    (net (code "27") (name "DC_X16") (class "Default")
      (node (ref "C16") (pin "1") (pinfunction "1_1") (pintype "passive"))
      (node (ref "OK15") (pin "4") (pinfunction "OUT_4") (pintype "output"))
      (node (ref "R62") (pin "2") (pinfunction "2_2") (pintype "passive"))
      (node (ref "U1") (pin "4") (pinfunction "P00_4") (pintype "bidirectional"))
    )
    (net (code "28") (name "GND") (class "Default")
      (node (ref "C1") (pin "2") (pinfunction "2_2") (pintype "passive"))
      (node (ref "C10") (pin "2") (pinfunction "2_2") (pintype "passive"))
      (node (ref "C11") (pin "2") (pinfunction "2_2") (pintype "passive"))
      (node (ref "C12") (pin "2") (pinfunction "2_2") (pintype "passive"))
      (node (ref "C13") (pin "2") (pinfunction "2_2") (pintype "passive"))
      (node (ref "C14") (pin "2") (pinfunction "2_2") (pintype "passive"))
      (node (ref "C15") (pin "2") (pinfunction "2_2") (pintype "passive"))
      (node (ref "C16") (pin "2") (pinfunction "2_2") (pintype "passive"))
      (node (ref "C2") (pin "2") (pinfunction "2_2") (pintype "passive"))
      (node (ref "C28") (pin "2") (pinfunction "2_2") (pintype "passive"))
      (node (ref "C3") (pin "2") (pinfunction "2_2") (pintype "passive"))
      (node (ref "C4") (pin "2") (pinfunction "2_2") (pintype "passive"))
      (node (ref "C5") (pin "2") (pinfunction "2_2") (pintype "passive"))
      (node (ref "C6") (pin "2") (pinfunction "2_2") (pintype "passive"))
      (node (ref "C7") (pin "2") (pinfunction "2_2") (pintype "passive"))
      (node (ref "C8") (pin "2") (pinfunction "2_2") (pintype "passive"))
      (node (ref "C9") (pin "2") (pinfunction "2_2") (pintype "passive"))
      (node (ref "J1") (pin "6") (pinfunction "S_6") (pintype "passive"))
      (node (ref "J3") (pin "6") (pinfunction "S_6") (pintype "passive"))
      (node (ref "OK0") (pin "5") (pinfunction "GND_5") (pintype "power_in"))
      (node (ref "OK1") (pin "5") (pinfunction "GND_5") (pintype "power_in"))
      (node (ref "OK10") (pin "5") (pinfunction "GND_5") (pintype "power_in"))
      (node (ref "OK11") (pin "5") (pinfunction "GND_5") (pintype "power_in"))
      (node (ref "OK12") (pin "5") (pinfunction "GND_5") (pintype "power_in"))
      (node (ref "OK13") (pin "5") (pinfunction "GND_5") (pintype "power_in"))
      (node (ref "OK14") (pin "5") (pinfunction "GND_5") (pintype "power_in"))
      (node (ref "OK15") (pin "5") (pinfunction "GND_5") (pintype "power_in"))
      (node (ref "OK2") (pin "5") (pinfunction "GND_5") (pintype "power_in"))
      (node (ref "OK3") (pin "5") (pinfunction "GND_5") (pintype "power_in"))
      (node (ref "OK4") (pin "5") (pinfunction "GND_5") (pintype "power_in"))
      (node (ref "OK5") (pin "5") (pinfunction "GND_5") (pintype "power_in"))
      (node (ref "OK6") (pin "5") (pinfunction "GND_5") (pintype "power_in"))
      (node (ref "OK7") (pin "5") (pinfunction "GND_5") (pintype "power_in"))
      (node (ref "OK8") (pin "5") (pinfunction "GND_5") (pintype "power_in"))
      (node (ref "OK9") (pin "5") (pinfunction "GND_5") (pintype "power_in"))
      (node (ref "SJ1") (pin "1") (pinfunction "1_1") (pintype "passive"))
      (node (ref "SJ2") (pin "1") (pinfunction "1_1") (pintype "passive"))
      (node (ref "SJ3") (pin "1") (pinfunction "1_1") (pintype "passive"))
      (node (ref "U1") (pin "12") (pinfunction "GND_12") (pintype "passive"))
    )
    (net (code "29") (name "IN_STIMN_D1") (class "Default")
      (node (ref "G1") (pin "A") (pinfunction "A_A") (pintype "passive"))
      (node (ref "G2") (pin "A") (pinfunction "A_A") (pintype "passive"))
      (node (ref "K3") (pin "8") (pinfunction "8_8") (pintype "passive"))
      (node (ref "OK0") (pin "2") (pinfunction "C_2") (pintype "passive"))
      (node (ref "R3") (pin "2") (pinfunction "2_2") (pintype "passive"))
      (node (ref "RED1") (pin "C") (pinfunction "C_C") (pintype "passive"))
      (node (ref "RED2") (pin "C") (pinfunction "C_C") (pintype "passive"))
    )
    (net (code "30") (name "IN_STIMN_D2") (class "Default")
      (node (ref "G3") (pin "A") (pinfunction "A_A") (pintype "passive"))
      (node (ref "G4") (pin "A") (pinfunction "A_A") (pintype "passive"))
      (node (ref "K3") (pin "11") (pinfunction "11_11") (pintype "passive"))
      (node (ref "OK1") (pin "2") (pinfunction "C_2") (pintype "passive"))
      (node (ref "R8") (pin "2") (pinfunction "2_2") (pintype "passive"))
      (node (ref "RED3") (pin "C") (pinfunction "C_C") (pintype "passive"))
      (node (ref "RED4") (pin "C") (pinfunction "C_C") (pintype "passive"))
    )
    (net (code "31") (name "IN_STIMN_D3") (class "Default")
      (node (ref "G5") (pin "A") (pinfunction "A_A") (pintype "passive"))
      (node (ref "G6") (pin "A") (pinfunction "A_A") (pintype "passive"))
      (node (ref "K3") (pin "6") (pinfunction "6_6") (pintype "passive"))
      (node (ref "OK2") (pin "2") (pinfunction "C_2") (pintype "passive"))
      (node (ref "R12") (pin "2") (pinfunction "2_2") (pintype "passive"))
      (node (ref "RED5") (pin "C") (pinfunction "C_C") (pintype "passive"))
      (node (ref "RED6") (pin "C") (pinfunction "C_C") (pintype "passive"))
    )
    (net (code "32") (name "IN_STIMN_D4") (class "Default")
      (node (ref "G7") (pin "A") (pinfunction "A_A") (pintype "passive"))
      (node (ref "G8") (pin "A") (pinfunction "A_A") (pintype "passive"))
      (node (ref "K3") (pin "12") (pinfunction "12_12") (pintype "passive"))
      (node (ref "OK3") (pin "2") (pinfunction "C_2") (pintype "passive"))
      (node (ref "R16") (pin "2") (pinfunction "2_2") (pintype "passive"))
      (node (ref "RED7") (pin "C") (pinfunction "C_C") (pintype "passive"))
      (node (ref "RED8") (pin "C") (pinfunction "C_C") (pintype "passive"))
    )
    (net (code "33") (name "IN_STIMN_D5") (class "Default")
      (node (ref "G10") (pin "A") (pinfunction "A_A") (pintype "passive"))
      (node (ref "G9") (pin "A") (pinfunction "A_A") (pintype "passive"))
      (node (ref "K3") (pin "7") (pinfunction "7_7") (pintype "passive"))
      (node (ref "OK4") (pin "2") (pinfunction "C_2") (pintype "passive"))
      (node (ref "R20") (pin "2") (pinfunction "2_2") (pintype "passive"))
      (node (ref "RED10") (pin "C") (pinfunction "C_C") (pintype "passive"))
      (node (ref "RED9") (pin "C") (pinfunction "C_C") (pintype "passive"))
    )
    (net (code "34") (name "IN_STIMN_D6") (class "Default")
      (node (ref "G11") (pin "A") (pinfunction "A_A") (pintype "passive"))
      (node (ref "G12") (pin "A") (pinfunction "A_A") (pintype "passive"))
      (node (ref "K3") (pin "10") (pinfunction "10_10") (pintype "passive"))
      (node (ref "OK5") (pin "2") (pinfunction "C_2") (pintype "passive"))
      (node (ref "R24") (pin "2") (pinfunction "2_2") (pintype "passive"))
      (node (ref "RED11") (pin "C") (pinfunction "C_C") (pintype "passive"))
      (node (ref "RED12") (pin "C") (pinfunction "C_C") (pintype "passive"))
    )
    (net (code "35") (name "IN_STIMN_D7") (class "Default")
      (node (ref "G13") (pin "A") (pinfunction "A_A") (pintype "passive"))
      (node (ref "G14") (pin "A") (pinfunction "A_A") (pintype "passive"))
      (node (ref "K3") (pin "9") (pinfunction "9_9") (pintype "passive"))
      (node (ref "OK6") (pin "2") (pinfunction "C_2") (pintype "passive"))
      (node (ref "R28") (pin "2") (pinfunction "2_2") (pintype "passive"))
      (node (ref "RED13") (pin "C") (pinfunction "C_C") (pintype "passive"))
      (node (ref "RED14") (pin "C") (pinfunction "C_C") (pintype "passive"))
    )
    (net (code "36") (name "IN_STIMN_D8") (class "Default")
      (node (ref "G15") (pin "A") (pinfunction "A_A") (pintype "passive"))
      (node (ref "G16") (pin "A") (pinfunction "A_A") (pintype "passive"))
      (node (ref "K3") (pin "3") (pinfunction "3_3") (pintype "passive"))
      (node (ref "OK7") (pin "2") (pinfunction "C_2") (pintype "passive"))
      (node (ref "R32") (pin "2") (pinfunction "2_2") (pintype "passive"))
      (node (ref "RED15") (pin "C") (pinfunction "C_C") (pintype "passive"))
      (node (ref "RED16") (pin "C") (pinfunction "C_C") (pintype "passive"))
    )
    (net (code "37") (name "IN_STIMN_D9") (class "Default")
      (node (ref "G17") (pin "A") (pinfunction "A_A") (pintype "passive"))
      (node (ref "G18") (pin "A") (pinfunction "A_A") (pintype "passive"))
      (node (ref "K3") (pin "15") (pinfunction "15_15") (pintype "passive"))
      (node (ref "OK8") (pin "2") (pinfunction "C_2") (pintype "passive"))
      (node (ref "R36") (pin "2") (pinfunction "2_2") (pintype "passive"))
      (node (ref "RED17") (pin "C") (pinfunction "C_C") (pintype "passive"))
      (node (ref "RED18") (pin "C") (pinfunction "C_C") (pintype "passive"))
    )
    (net (code "38") (name "IN_STIMN_D10") (class "Default")
      (node (ref "G19") (pin "A") (pinfunction "A_A") (pintype "passive"))
      (node (ref "G20") (pin "A") (pinfunction "A_A") (pintype "passive"))
      (node (ref "K3") (pin "14") (pinfunction "14_14") (pintype "passive"))
      (node (ref "OK9") (pin "2") (pinfunction "C_2") (pintype "passive"))
      (node (ref "R40") (pin "2") (pinfunction "2_2") (pintype "passive"))
      (node (ref "RED19") (pin "C") (pinfunction "C_C") (pintype "passive"))
      (node (ref "RED20") (pin "C") (pinfunction "C_C") (pintype "passive"))
    )
    (net (code "39") (name "IN_STIMN_D11") (class "Default")
      (node (ref "G21") (pin "A") (pinfunction "A_A") (pintype "passive"))
      (node (ref "G22") (pin "A") (pinfunction "A_A") (pintype "passive"))
      (node (ref "K3") (pin "4") (pinfunction "4_4") (pintype "passive"))
      (node (ref "OK10") (pin "2") (pinfunction "C_2") (pintype "passive"))
      (node (ref "R44") (pin "2") (pinfunction "2_2") (pintype "passive"))
      (node (ref "RED21") (pin "C") (pinfunction "C_C") (pintype "passive"))
      (node (ref "RED22") (pin "C") (pinfunction "C_C") (pintype "passive"))
    )
    (net (code "40") (name "IN_STIMN_D12") (class "Default")
      (node (ref "G23") (pin "A") (pinfunction "A_A") (pintype "passive"))
      (node (ref "G24") (pin "A") (pinfunction "A_A") (pintype "passive"))
      (node (ref "K3") (pin "13") (pinfunction "13_13") (pintype "passive"))
      (node (ref "OK11") (pin "2") (pinfunction "C_2") (pintype "passive"))
      (node (ref "R48") (pin "2") (pinfunction "2_2") (pintype "passive"))
      (node (ref "RED23") (pin "C") (pinfunction "C_C") (pintype "passive"))
      (node (ref "RED24") (pin "C") (pinfunction "C_C") (pintype "passive"))
    )
    (net (code "41") (name "IN_STIMN_D13") (class "Default")
      (node (ref "G25") (pin "A") (pinfunction "A_A") (pintype "passive"))
      (node (ref "G26") (pin "A") (pinfunction "A_A") (pintype "passive"))
      (node (ref "K3") (pin "5") (pinfunction "5_5") (pintype "passive"))
      (node (ref "OK12") (pin "2") (pinfunction "C_2") (pintype "passive"))
      (node (ref "R52") (pin "2") (pinfunction "2_2") (pintype "passive"))
      (node (ref "RED25") (pin "C") (pinfunction "C_C") (pintype "passive"))
      (node (ref "RED26") (pin "C") (pinfunction "C_C") (pintype "passive"))
    )
    (net (code "42") (name "IN_STIMN_D14") (class "Default")
      (node (ref "G27") (pin "A") (pinfunction "A_A") (pintype "passive"))
      (node (ref "G28") (pin "A") (pinfunction "A_A") (pintype "passive"))
      (node (ref "K3") (pin "2") (pinfunction "2_2") (pintype "passive"))
      (node (ref "OK13") (pin "2") (pinfunction "C_2") (pintype "passive"))
      (node (ref "R56") (pin "2") (pinfunction "2_2") (pintype "passive"))
      (node (ref "RED27") (pin "C") (pinfunction "C_C") (pintype "passive"))
      (node (ref "RED28") (pin "C") (pinfunction "C_C") (pintype "passive"))
    )
    (net (code "43") (name "IN_STIMN_D15") (class "Default")
      (node (ref "G29") (pin "A") (pinfunction "A_A") (pintype "passive"))
      (node (ref "G30") (pin "A") (pinfunction "A_A") (pintype "passive"))
      (node (ref "K3") (pin "1") (pinfunction "1_1") (pintype "passive"))
      (node (ref "OK14") (pin "2") (pinfunction "C_2") (pintype "passive"))
      (node (ref "R60") (pin "2") (pinfunction "2_2") (pintype "passive"))
      (node (ref "RED29") (pin "C") (pinfunction "C_C") (pintype "passive"))
      (node (ref "RED30") (pin "C") (pinfunction "C_C") (pintype "passive"))
    )
    (net (code "44") (name "IN_STIMN_D16") (class "Default")
      (node (ref "G31") (pin "A") (pinfunction "A_A") (pintype "passive"))
      (node (ref "G32") (pin "A") (pinfunction "A_A") (pintype "passive"))
      (node (ref "K3") (pin "16") (pinfunction "16_16") (pintype "passive"))
      (node (ref "OK15") (pin "2") (pinfunction "C_2") (pintype "passive"))
      (node (ref "R64") (pin "2") (pinfunction "2_2") (pintype "passive"))
      (node (ref "RED31") (pin "C") (pinfunction "C_C") (pintype "passive"))
      (node (ref "RED32") (pin "C") (pinfunction "C_C") (pintype "passive"))
    )
    (net (code "45") (name "IN_STIMP_D1") (class "Default")
      (node (ref "G1") (pin "C") (pinfunction "C_C") (pintype "passive"))
      (node (ref "G2") (pin "C") (pinfunction "C_C") (pintype "passive"))
      (node (ref "K2") (pin "8") (pinfunction "8_8") (pintype "passive"))
      (node (ref "R1") (pin "2") (pinfunction "2_2") (pintype "passive"))
      (node (ref "R2") (pin "2") (pinfunction "2_2") (pintype "passive"))
      (node (ref "RED1") (pin "A") (pinfunction "A_A") (pintype "passive"))
      (node (ref "RED2") (pin "A") (pinfunction "A_A") (pintype "passive"))
    )
    (net (code "46") (name "IN_STIMP_D2") (class "Default")
      (node (ref "G3") (pin "C") (pinfunction "C_C") (pintype "passive"))
      (node (ref "G4") (pin "C") (pinfunction "C_C") (pintype "passive"))
      (node (ref "K2") (pin "6") (pinfunction "6_6") (pintype "passive"))
      (node (ref "R5") (pin "2") (pinfunction "2_2") (pintype "passive"))
      (node (ref "R7") (pin "2") (pinfunction "2_2") (pintype "passive"))
      (node (ref "RED3") (pin "A") (pinfunction "A_A") (pintype "passive"))
      (node (ref "RED4") (pin "A") (pinfunction "A_A") (pintype "passive"))
    )
    (net (code "47") (name "IN_STIMP_D3") (class "Default")
      (node (ref "G5") (pin "C") (pinfunction "C_C") (pintype "passive"))
      (node (ref "G6") (pin "C") (pinfunction "C_C") (pintype "passive"))
      (node (ref "K2") (pin "11") (pinfunction "11_11") (pintype "passive"))
      (node (ref "R11") (pin "2") (pinfunction "2_2") (pintype "passive"))
      (node (ref "R9") (pin "2") (pinfunction "2_2") (pintype "passive"))
      (node (ref "RED5") (pin "A") (pinfunction "A_A") (pintype "passive"))
      (node (ref "RED6") (pin "A") (pinfunction "A_A") (pintype "passive"))
    )
    (net (code "48") (name "IN_STIMP_D4") (class "Default")
      (node (ref "G7") (pin "C") (pinfunction "C_C") (pintype "passive"))
      (node (ref "G8") (pin "C") (pinfunction "C_C") (pintype "passive"))
      (node (ref "K2") (pin "5") (pinfunction "5_5") (pintype "passive"))
      (node (ref "R13") (pin "2") (pinfunction "2_2") (pintype "passive"))
      (node (ref "R15") (pin "2") (pinfunction "2_2") (pintype "passive"))
      (node (ref "RED7") (pin "A") (pinfunction "A_A") (pintype "passive"))
      (node (ref "RED8") (pin "A") (pinfunction "A_A") (pintype "passive"))
    )
    (net (code "49") (name "IN_STIMP_D5") (class "Default")
      (node (ref "G10") (pin "C") (pinfunction "C_C") (pintype "passive"))
      (node (ref "G9") (pin "C") (pinfunction "C_C") (pintype "passive"))
      (node (ref "K2") (pin "10") (pinfunction "10_10") (pintype "passive"))
      (node (ref "R17") (pin "2") (pinfunction "2_2") (pintype "passive"))
      (node (ref "R19") (pin "2") (pinfunction "2_2") (pintype "passive"))
      (node (ref "RED10") (pin "A") (pinfunction "A_A") (pintype "passive"))
      (node (ref "RED9") (pin "A") (pinfunction "A_A") (pintype "passive"))
    )
    (net (code "50") (name "IN_STIMP_D6") (class "Default")
      (node (ref "G11") (pin "C") (pinfunction "C_C") (pintype "passive"))
      (node (ref "G12") (pin "C") (pinfunction "C_C") (pintype "passive"))
      (node (ref "K2") (pin "7") (pinfunction "7_7") (pintype "passive"))
      (node (ref "R21") (pin "2") (pinfunction "2_2") (pintype "passive"))
      (node (ref "R23") (pin "2") (pinfunction "2_2") (pintype "passive"))
      (node (ref "RED11") (pin "A") (pinfunction "A_A") (pintype "passive"))
      (node (ref "RED12") (pin "A") (pinfunction "A_A") (pintype "passive"))
    )
    (net (code "51") (name "IN_STIMP_D7") (class "Default")
      (node (ref "G13") (pin "C") (pinfunction "C_C") (pintype "passive"))
      (node (ref "G14") (pin "C") (pinfunction "C_C") (pintype "passive"))
      (node (ref "K2") (pin "9") (pinfunction "9_9") (pintype "passive"))
      (node (ref "R25") (pin "2") (pinfunction "2_2") (pintype "passive"))
      (node (ref "R27") (pin "2") (pinfunction "2_2") (pintype "passive"))
      (node (ref "RED13") (pin "A") (pinfunction "A_A") (pintype "passive"))
      (node (ref "RED14") (pin "A") (pinfunction "A_A") (pintype "passive"))
    )
    (net (code "52") (name "IN_STIMP_D8") (class "Default")
      (node (ref "G15") (pin "C") (pinfunction "C_C") (pintype "passive"))
      (node (ref "G16") (pin "C") (pinfunction "C_C") (pintype "passive"))
      (node (ref "K2") (pin "3") (pinfunction "3_3") (pintype "passive"))
      (node (ref "R29") (pin "2") (pinfunction "2_2") (pintype "passive"))
      (node (ref "R31") (pin "2") (pinfunction "2_2") (pintype "passive"))
      (node (ref "RED15") (pin "A") (pinfunction "A_A") (pintype "passive"))
      (node (ref "RED16") (pin "A") (pinfunction "A_A") (pintype "passive"))
    )
    (net (code "53") (name "IN_STIMP_D9") (class "Default")
      (node (ref "G17") (pin "C") (pinfunction "C_C") (pintype "passive"))
      (node (ref "G18") (pin "C") (pinfunction "C_C") (pintype "passive"))
      (node (ref "K2") (pin "15") (pinfunction "15_15") (pintype "passive"))
      (node (ref "R33") (pin "2") (pinfunction "2_2") (pintype "passive"))
      (node (ref "R35") (pin "2") (pinfunction "2_2") (pintype "passive"))
      (node (ref "RED17") (pin "A") (pinfunction "A_A") (pintype "passive"))
      (node (ref "RED18") (pin "A") (pinfunction "A_A") (pintype "passive"))
    )
    (net (code "54") (name "IN_STIMP_D10") (class "Default")
      (node (ref "G19") (pin "C") (pinfunction "C_C") (pintype "passive"))
      (node (ref "G20") (pin "C") (pinfunction "C_C") (pintype "passive"))
      (node (ref "K2") (pin "14") (pinfunction "14_14") (pintype "passive"))
      (node (ref "R37") (pin "2") (pinfunction "2_2") (pintype "passive"))
      (node (ref "R39") (pin "2") (pinfunction "2_2") (pintype "passive"))
      (node (ref "RED19") (pin "A") (pinfunction "A_A") (pintype "passive"))
      (node (ref "RED20") (pin "A") (pinfunction "A_A") (pintype "passive"))
    )
    (net (code "55") (name "IN_STIMP_D11") (class "Default")
      (node (ref "G21") (pin "C") (pinfunction "C_C") (pintype "passive"))
      (node (ref "G22") (pin "C") (pinfunction "C_C") (pintype "passive"))
      (node (ref "K2") (pin "13") (pinfunction "13_13") (pintype "passive"))
      (node (ref "R41") (pin "2") (pinfunction "2_2") (pintype "passive"))
      (node (ref "R43") (pin "2") (pinfunction "2_2") (pintype "passive"))
      (node (ref "RED21") (pin "A") (pinfunction "A_A") (pintype "passive"))
      (node (ref "RED22") (pin "A") (pinfunction "A_A") (pintype "passive"))
    )
    (net (code "56") (name "IN_STIMP_D12") (class "Default")
      (node (ref "G23") (pin "C") (pinfunction "C_C") (pintype "passive"))
      (node (ref "G24") (pin "C") (pinfunction "C_C") (pintype "passive"))
      (node (ref "K2") (pin "4") (pinfunction "4_4") (pintype "passive"))
      (node (ref "R45") (pin "2") (pinfunction "2_2") (pintype "passive"))
      (node (ref "R47") (pin "2") (pinfunction "2_2") (pintype "passive"))
      (node (ref "RED23") (pin "A") (pinfunction "A_A") (pintype "passive"))
      (node (ref "RED24") (pin "A") (pinfunction "A_A") (pintype "passive"))
    )
    (net (code "57") (name "IN_STIMP_D13") (class "Default")
      (node (ref "G25") (pin "C") (pinfunction "C_C") (pintype "passive"))
      (node (ref "G26") (pin "C") (pinfunction "C_C") (pintype "passive"))
      (node (ref "K2") (pin "12") (pinfunction "12_12") (pintype "passive"))
      (node (ref "R49") (pin "2") (pinfunction "2_2") (pintype "passive"))
      (node (ref "R51") (pin "2") (pinfunction "2_2") (pintype "passive"))
      (node (ref "RED25") (pin "A") (pinfunction "A_A") (pintype "passive"))
      (node (ref "RED26") (pin "A") (pinfunction "A_A") (pintype "passive"))
    )
    (net (code "58") (name "IN_STIMP_D14") (class "Default")
      (node (ref "G27") (pin "C") (pinfunction "C_C") (pintype "passive"))
      (node (ref "G28") (pin "C") (pinfunction "C_C") (pintype "passive"))
      (node (ref "K2") (pin "2") (pinfunction "2_2") (pintype "passive"))
      (node (ref "R53") (pin "2") (pinfunction "2_2") (pintype "passive"))
      (node (ref "R55") (pin "2") (pinfunction "2_2") (pintype "passive"))
      (node (ref "RED27") (pin "A") (pinfunction "A_A") (pintype "passive"))
      (node (ref "RED28") (pin "A") (pinfunction "A_A") (pintype "passive"))
    )
    (net (code "59") (name "IN_STIMP_D15") (class "Default")
      (node (ref "G29") (pin "C") (pinfunction "C_C") (pintype "passive"))
      (node (ref "G30") (pin "C") (pinfunction "C_C") (pintype "passive"))
      (node (ref "K2") (pin "16") (pinfunction "16_16") (pintype "passive"))
      (node (ref "R57") (pin "2") (pinfunction "2_2") (pintype "passive"))
      (node (ref "R59") (pin "2") (pinfunction "2_2") (pintype "passive"))
      (node (ref "RED29") (pin "A") (pinfunction "A_A") (pintype "passive"))
      (node (ref "RED30") (pin "A") (pinfunction "A_A") (pintype "passive"))
    )
    (net (code "60") (name "IN_STIMP_D16") (class "Default")
      (node (ref "G31") (pin "C") (pinfunction "C_C") (pintype "passive"))
      (node (ref "G32") (pin "C") (pinfunction "C_C") (pintype "passive"))
      (node (ref "K2") (pin "1") (pinfunction "1_1") (pintype "passive"))
      (node (ref "R61") (pin "2") (pinfunction "2_2") (pintype "passive"))
      (node (ref "R63") (pin "2") (pinfunction "2_2") (pintype "passive"))
      (node (ref "RED31") (pin "A") (pinfunction "A_A") (pintype "passive"))
      (node (ref "RED32") (pin "A") (pinfunction "A_A") (pintype "passive"))
    )
    (net (code "61") (name "Net-(OK0-A)") (class "Default")
      (node (ref "OK0") (pin "1") (pinfunction "A_1") (pintype "passive"))
      (node (ref "R1") (pin "1") (pinfunction "1_1") (pintype "passive"))
    )
    (net (code "62") (name "Net-(OK1-A)") (class "Default")
      (node (ref "OK1") (pin "1") (pinfunction "A_1") (pintype "passive"))
      (node (ref "R5") (pin "1") (pinfunction "1_1") (pintype "passive"))
    )
    (net (code "63") (name "Net-(OK2-A)") (class "Default")
      (node (ref "OK2") (pin "1") (pinfunction "A_1") (pintype "passive"))
      (node (ref "R9") (pin "1") (pinfunction "1_1") (pintype "passive"))
    )
    (net (code "64") (name "Net-(OK3-A)") (class "Default")
      (node (ref "OK3") (pin "1") (pinfunction "A_1") (pintype "passive"))
      (node (ref "R13") (pin "1") (pinfunction "1_1") (pintype "passive"))
    )
    (net (code "65") (name "Net-(OK4-A)") (class "Default")
      (node (ref "OK4") (pin "1") (pinfunction "A_1") (pintype "passive"))
      (node (ref "R17") (pin "1") (pinfunction "1_1") (pintype "passive"))
    )
    (net (code "66") (name "Net-(OK5-A)") (class "Default")
      (node (ref "OK5") (pin "1") (pinfunction "A_1") (pintype "passive"))
      (node (ref "R21") (pin "1") (pinfunction "1_1") (pintype "passive"))
    )
    (net (code "67") (name "Net-(OK6-A)") (class "Default")
      (node (ref "OK6") (pin "1") (pinfunction "A_1") (pintype "passive"))
      (node (ref "R25") (pin "1") (pinfunction "1_1") (pintype "passive"))
    )
    (net (code "68") (name "Net-(OK7-A)") (class "Default")
      (node (ref "OK7") (pin "1") (pinfunction "A_1") (pintype "passive"))
      (node (ref "R29") (pin "1") (pinfunction "1_1") (pintype "passive"))
    )
    (net (code "69") (name "Net-(OK8-A)") (class "Default")
      (node (ref "OK8") (pin "1") (pinfunction "A_1") (pintype "passive"))
      (node (ref "R33") (pin "1") (pinfunction "1_1") (pintype "passive"))
    )
    (net (code "70") (name "Net-(OK9-A)") (class "Default")
      (node (ref "OK9") (pin "1") (pinfunction "A_1") (pintype "passive"))
      (node (ref "R37") (pin "1") (pinfunction "1_1") (pintype "passive"))
    )
    (net (code "71") (name "Net-(OK10-A)") (class "Default")
      (node (ref "OK10") (pin "1") (pinfunction "A_1") (pintype "passive"))
      (node (ref "R41") (pin "1") (pinfunction "1_1") (pintype "passive"))
    )
    (net (code "72") (name "Net-(OK11-A)") (class "Default")
      (node (ref "OK11") (pin "1") (pinfunction "A_1") (pintype "passive"))
      (node (ref "R45") (pin "1") (pinfunction "1_1") (pintype "passive"))
    )
    (net (code "73") (name "Net-(OK12-A)") (class "Default")
      (node (ref "OK12") (pin "1") (pinfunction "A_1") (pintype "passive"))
      (node (ref "R49") (pin "1") (pinfunction "1_1") (pintype "passive"))
    )
    (net (code "74") (name "Net-(OK13-A)") (class "Default")
      (node (ref "OK13") (pin "1") (pinfunction "A_1") (pintype "passive"))
      (node (ref "R53") (pin "1") (pinfunction "1_1") (pintype "passive"))
    )
    (net (code "75") (name "Net-(OK14-A)") (class "Default")
      (node (ref "OK14") (pin "1") (pinfunction "A_1") (pintype "passive"))
      (node (ref "R57") (pin "1") (pinfunction "1_1") (pintype "passive"))
    )
    (net (code "76") (name "Net-(OK15-A)") (class "Default")
      (node (ref "OK15") (pin "1") (pinfunction "A_1") (pintype "passive"))
      (node (ref "R61") (pin "1") (pinfunction "1_1") (pintype "passive"))
    )
    (net (code "77") (name "Net-(U1-A0)") (class "Default")
      (node (ref "SJ1") (pin "2") (pinfunction "2_2") (pintype "passive"))
      (node (ref "U1") (pin "21") (pinfunction "A0_21") (pintype "input"))
    )
    (net (code "78") (name "Net-(U1-A1)") (class "Default")
      (node (ref "SJ2") (pin "2") (pinfunction "2_2") (pintype "passive"))
      (node (ref "U1") (pin "2") (pinfunction "A1_2") (pintype "input"))
    )
    (net (code "79") (name "Net-(U1-A2)") (class "Default")
      (node (ref "SJ3") (pin "2") (pinfunction "2_2") (pintype "passive"))
      (node (ref "U1") (pin "3") (pinfunction "A2_3") (pintype "input"))
    )
    (net (code "80") (name "SCL") (class "Default")
      (node (ref "SJ4") (pin "2") (pinfunction "2_2") (pintype "passive"))
      (node (ref "U1") (pin "22") (pinfunction "SCL_22") (pintype "input"))
    )
    (net (code "81") (name "SDA") (class "Default")
      (node (ref "SJ5") (pin "2") (pinfunction "2_2") (pintype "passive"))
      (node (ref "U1") (pin "23") (pinfunction "SDA_23") (pintype "bidirectional"))
    )
    (net (code "82") (name "STIMN") (class "Default")
      (node (ref "R11") (pin "1") (pinfunction "1_1") (pintype "passive"))
      (node (ref "R15") (pin "1") (pinfunction "1_1") (pintype "passive"))
      (node (ref "R19") (pin "1") (pinfunction "1_1") (pintype "passive"))
      (node (ref "R2") (pin "1") (pinfunction "1_1") (pintype "passive"))
      (node (ref "R23") (pin "1") (pinfunction "1_1") (pintype "passive"))
      (node (ref "R27") (pin "1") (pinfunction "1_1") (pintype "passive"))
      (node (ref "R31") (pin "1") (pinfunction "1_1") (pintype "passive"))
      (node (ref "R35") (pin "1") (pinfunction "1_1") (pintype "passive"))
      (node (ref "R39") (pin "1") (pinfunction "1_1") (pintype "passive"))
      (node (ref "R43") (pin "1") (pinfunction "1_1") (pintype "passive"))
      (node (ref "R47") (pin "1") (pinfunction "1_1") (pintype "passive"))
      (node (ref "R51") (pin "1") (pinfunction "1_1") (pintype "passive"))
      (node (ref "R55") (pin "1") (pinfunction "1_1") (pintype "passive"))
      (node (ref "R59") (pin "1") (pinfunction "1_1") (pintype "passive"))
      (node (ref "R63") (pin "1") (pinfunction "1_1") (pintype "passive"))
      (node (ref "R7") (pin "1") (pinfunction "1_1") (pintype "passive"))
      (node (ref "R70") (pin "2") (pinfunction "2_2") (pintype "passive"))
    )
    (net (code "83") (name "STIMP") (class "Default")
      (node (ref "R12") (pin "1") (pinfunction "1_1") (pintype "passive"))
      (node (ref "R16") (pin "1") (pinfunction "1_1") (pintype "passive"))
      (node (ref "R20") (pin "1") (pinfunction "1_1") (pintype "passive"))
      (node (ref "R24") (pin "1") (pinfunction "1_1") (pintype "passive"))
      (node (ref "R28") (pin "1") (pinfunction "1_1") (pintype "passive"))
      (node (ref "R3") (pin "1") (pinfunction "1_1") (pintype "passive"))
      (node (ref "R32") (pin "1") (pinfunction "1_1") (pintype "passive"))
      (node (ref "R36") (pin "1") (pinfunction "1_1") (pintype "passive"))
      (node (ref "R40") (pin "1") (pinfunction "1_1") (pintype "passive"))
      (node (ref "R44") (pin "1") (pinfunction "1_1") (pintype "passive"))
      (node (ref "R48") (pin "1") (pinfunction "1_1") (pintype "passive"))
      (node (ref "R52") (pin "1") (pinfunction "1_1") (pintype "passive"))
      (node (ref "R56") (pin "1") (pinfunction "1_1") (pintype "passive"))
      (node (ref "R60") (pin "1") (pinfunction "1_1") (pintype "passive"))
      (node (ref "R64") (pin "1") (pinfunction "1_1") (pintype "passive"))
      (node (ref "R71") (pin "2") (pinfunction "2_2") (pintype "passive"))
      (node (ref "R8") (pin "1") (pinfunction "1_1") (pintype "passive"))
    )
    (net (code "84") (name "unconnected-(J1G-S-Pad4)") (class "Default")
      (node (ref "J1") (pin "4") (pinfunction "S_4") (pintype "passive"))
    )
    (net (code "85") (name "unconnected-(J3G-S-Pad4)") (class "Default")
      (node (ref "J3") (pin "4") (pinfunction "S_4") (pintype "passive"))
    )
  )
)
